# enc_read.net
KiCad netlist of a schematic drawn in EAGLE
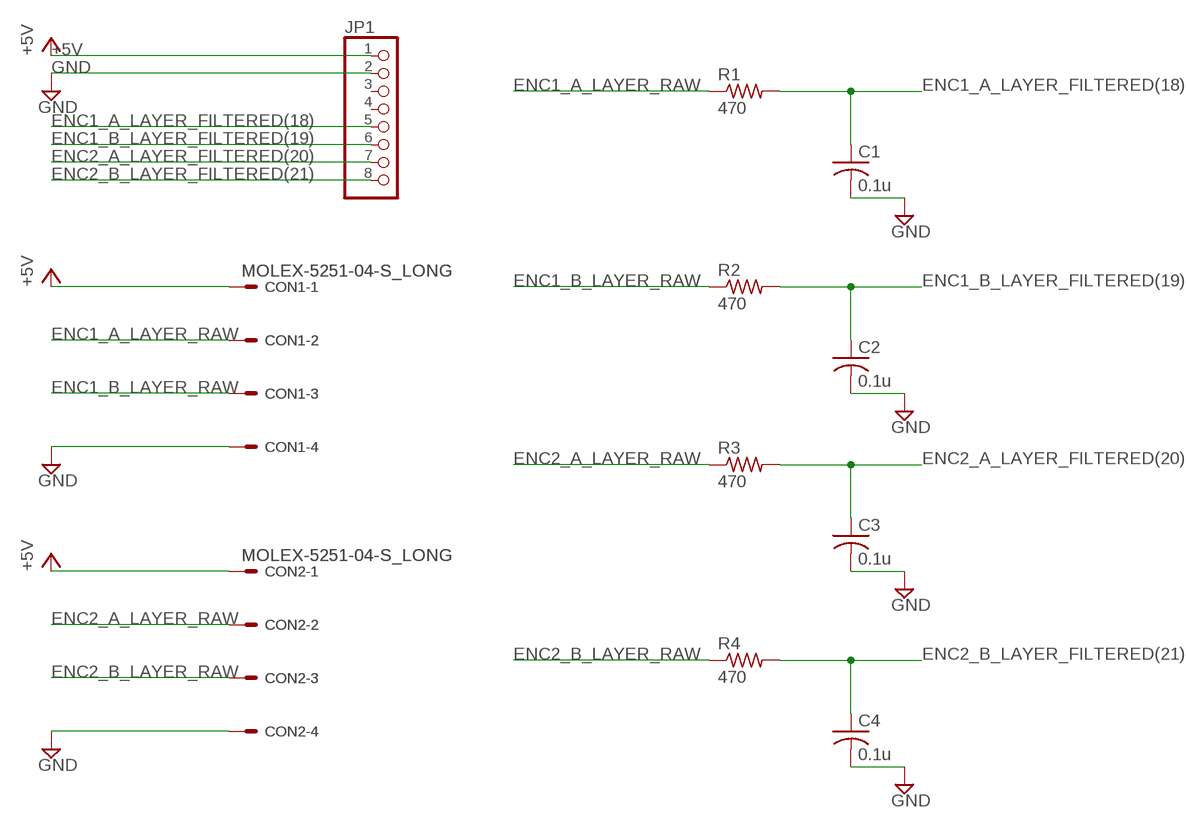
[diagram p0: schematic, sheet 1]

(export (version "E")
  (design (tool "Eeschema 10.0.6"))
  (components
    (comp (ref "C1")
      (value "0.1u")
      (footprint "eagle-import:2012-C")
      (libsource (lib "eagle-import") (part "C-2012"))
    )
    (comp (ref "C2")
      (value "0.1u")
      (footprint "eagle-import:2012-C")
      (libsource (lib "eagle-import") (part "C-2012"))
    )
    (comp (ref "C3")
      (value "0.1u")
      (footprint "eagle-import:2012-C")
      (libsource (lib "eagle-import") (part "C-2012"))
    )
    (comp (ref "C4")
      (value "0.1u")
      (footprint "eagle-import:2012-C")
      (libsource (lib "eagle-import") (part "C-2012"))
    )
    (comp (ref "CON1")
      (value "MOLEX-5251-04-S_LONG")
      (footprint "eagle-import:5251-04-S_LONG")
      (libsource (lib "eagle-import") (part "MOLEX-5251-04-S_LONG"))
    )
    (comp (ref "CON2")
      (value "MOLEX-5251-04-S_LONG")
      (footprint "eagle-import:5251-04-S_LONG")
      (libsource (lib "eagle-import") (part "MOLEX-5251-04-S_LONG"))
    )
    (comp (ref "JP1")
      (value "PINHD-1X8")
      (footprint "eagle-import:1X08")
      (libsource (lib "eagle-import") (part "PINHD-1X8"))
    )
    (comp (ref "R1")
      (value "470")
      (footprint "eagle-import:2012-R")
      (libsource (lib "eagle-import") (part "R-2012"))
    )
    (comp (ref "R2")
      (value "470")
      (footprint "eagle-import:2012-R")
      (libsource (lib "eagle-import") (part "R-2012"))
    )
    (comp (ref "R3")
      (value "470")
      (footprint "eagle-import:2012-R")
      (libsource (lib "eagle-import") (part "R-2012"))
    )
    (comp (ref "R4")
      (value "470")
      (footprint "eagle-import:2012-R")
      (libsource (lib "eagle-import") (part "R-2012"))
    )
  )
  (nets
    (net (code "1") (name "+5V") (class "Default")
      (node (ref "CON1") (pin "1") (pinfunction "S_1") (pintype "passive"))
      (node (ref "CON2") (pin "1") (pinfunction "S_1") (pintype "passive"))
      (node (ref "JP1") (pin "1") (pinfunction "1_1") (pintype "passive"))
    )
    (net (code "2") (name "/ENC1_A_LAYER_FILTERED(18)") (class "Default")
      (node (ref "C1") (pin "1") (pinfunction "1_1") (pintype "passive"))
      (node (ref "JP1") (pin "5") (pinfunction "5_5") (pintype "passive"))
      (node (ref "R1") (pin "2") (pinfunction "2_2") (pintype "passive"))
    )
    (net (code "3") (name "/ENC1_A_LAYER_RAW") (class "Default")
      (node (ref "CON1") (pin "2") (pinfunction "S_2") (pintype "passive"))
      (node (ref "R1") (pin "1") (pinfunction "1_1") (pintype "passive"))
    )
    (net (code "4") (name "/ENC1_B_LAYER_FILTERED(19)") (class "Default")
      (node (ref "C2") (pin "1") (pinfunction "1_1") (pintype "passive"))
      (node (ref "JP1") (pin "6") (pinfunction "6_6") (pintype "passive"))
      (node (ref "R2") (pin "2") (pinfunction "2_2") (pintype "passive"))
    )
    (net (code "5") (name "/ENC1_B_LAYER_RAW") (class "Default")
      (node (ref "CON1") (pin "3") (pinfunction "S_3") (pintype "passive"))
      (node (ref "R2") (pin "1") (pinfunction "1_1") (pintype "passive"))
    )
    (net (code "6") (name "/ENC2_A_LAYER_FILTERED(20)") (class "Default")
      (node (ref "C3") (pin "1") (pinfunction "1_1") (pintype "passive"))
      (node (ref "JP1") (pin "7") (pinfunction "7_7") (pintype "passive"))
      (node (ref "R3") (pin "2") (pinfunction "2_2") (pintype "passive"))
    )
    (net (code "7") (name "/ENC2_A_LAYER_RAW") (class "Default")
      (node (ref "CON2") (pin "2") (pinfunction "S_2") (pintype "passive"))
      (node (ref "R3") (pin "1") (pinfunction "1_1") (pintype "passive"))
    )
    (net (code "8") (name "/ENC2_B_LAYER_FILTERED(21)") (class "Default")
      (node (ref "C4") (pin "1") (pinfunction "1_1") (pintype "passive"))
      (node (ref "JP1") (pin "8") (pinfunction "8_8") (pintype "passive"))
      (node (ref "R4") (pin "2") (pinfunction "2_2") (pintype "passive"))
    )
    (net (code "9") (name "/ENC2_B_LAYER_RAW") (class "Default")
      (node (ref "CON2") (pin "3") (pinfunction "S_3") (pintype "passive"))
      (node (ref "R4") (pin "1") (pinfunction "1_1") (pintype "passive"))
    )
    (net (code "10") (name "GND") (class "Default")
      (node (ref "C1") (pin "2") (pinfunction "2_2") (pintype "passive"))
      (node (ref "C2") (pin "2") (pinfunction "2_2") (pintype "passive"))
      (node (ref "C3") (pin "2") (pinfunction "2_2") (pintype "passive"))
      (node (ref "C4") (pin "2") (pinfunction "2_2") (pintype "passive"))
      (node (ref "CON1") (pin "4") (pinfunction "S_4") (pintype "passive"))
      (node (ref "CON2") (pin "4") (pinfunction "S_4") (pintype "passive"))
      (node (ref "JP1") (pin "2") (pinfunction "2_2") (pintype "passive"))
    )
    (net (code "11") (name "unconnected-(JP1-Pad3)") (class "Default")
      (node (ref "JP1") (pin "3") (pinfunction "3_3") (pintype "passive"))
    )
    (net (code "12") (name "unconnected-(JP1-Pad4)") (class "Default")
      (node (ref "JP1") (pin "4") (pinfunction "4_4") (pintype "passive"))
    )
  )
)
